# 15P1D_EDA.net
KiCad netlist of a schematic drawn in EasyEDA Pro
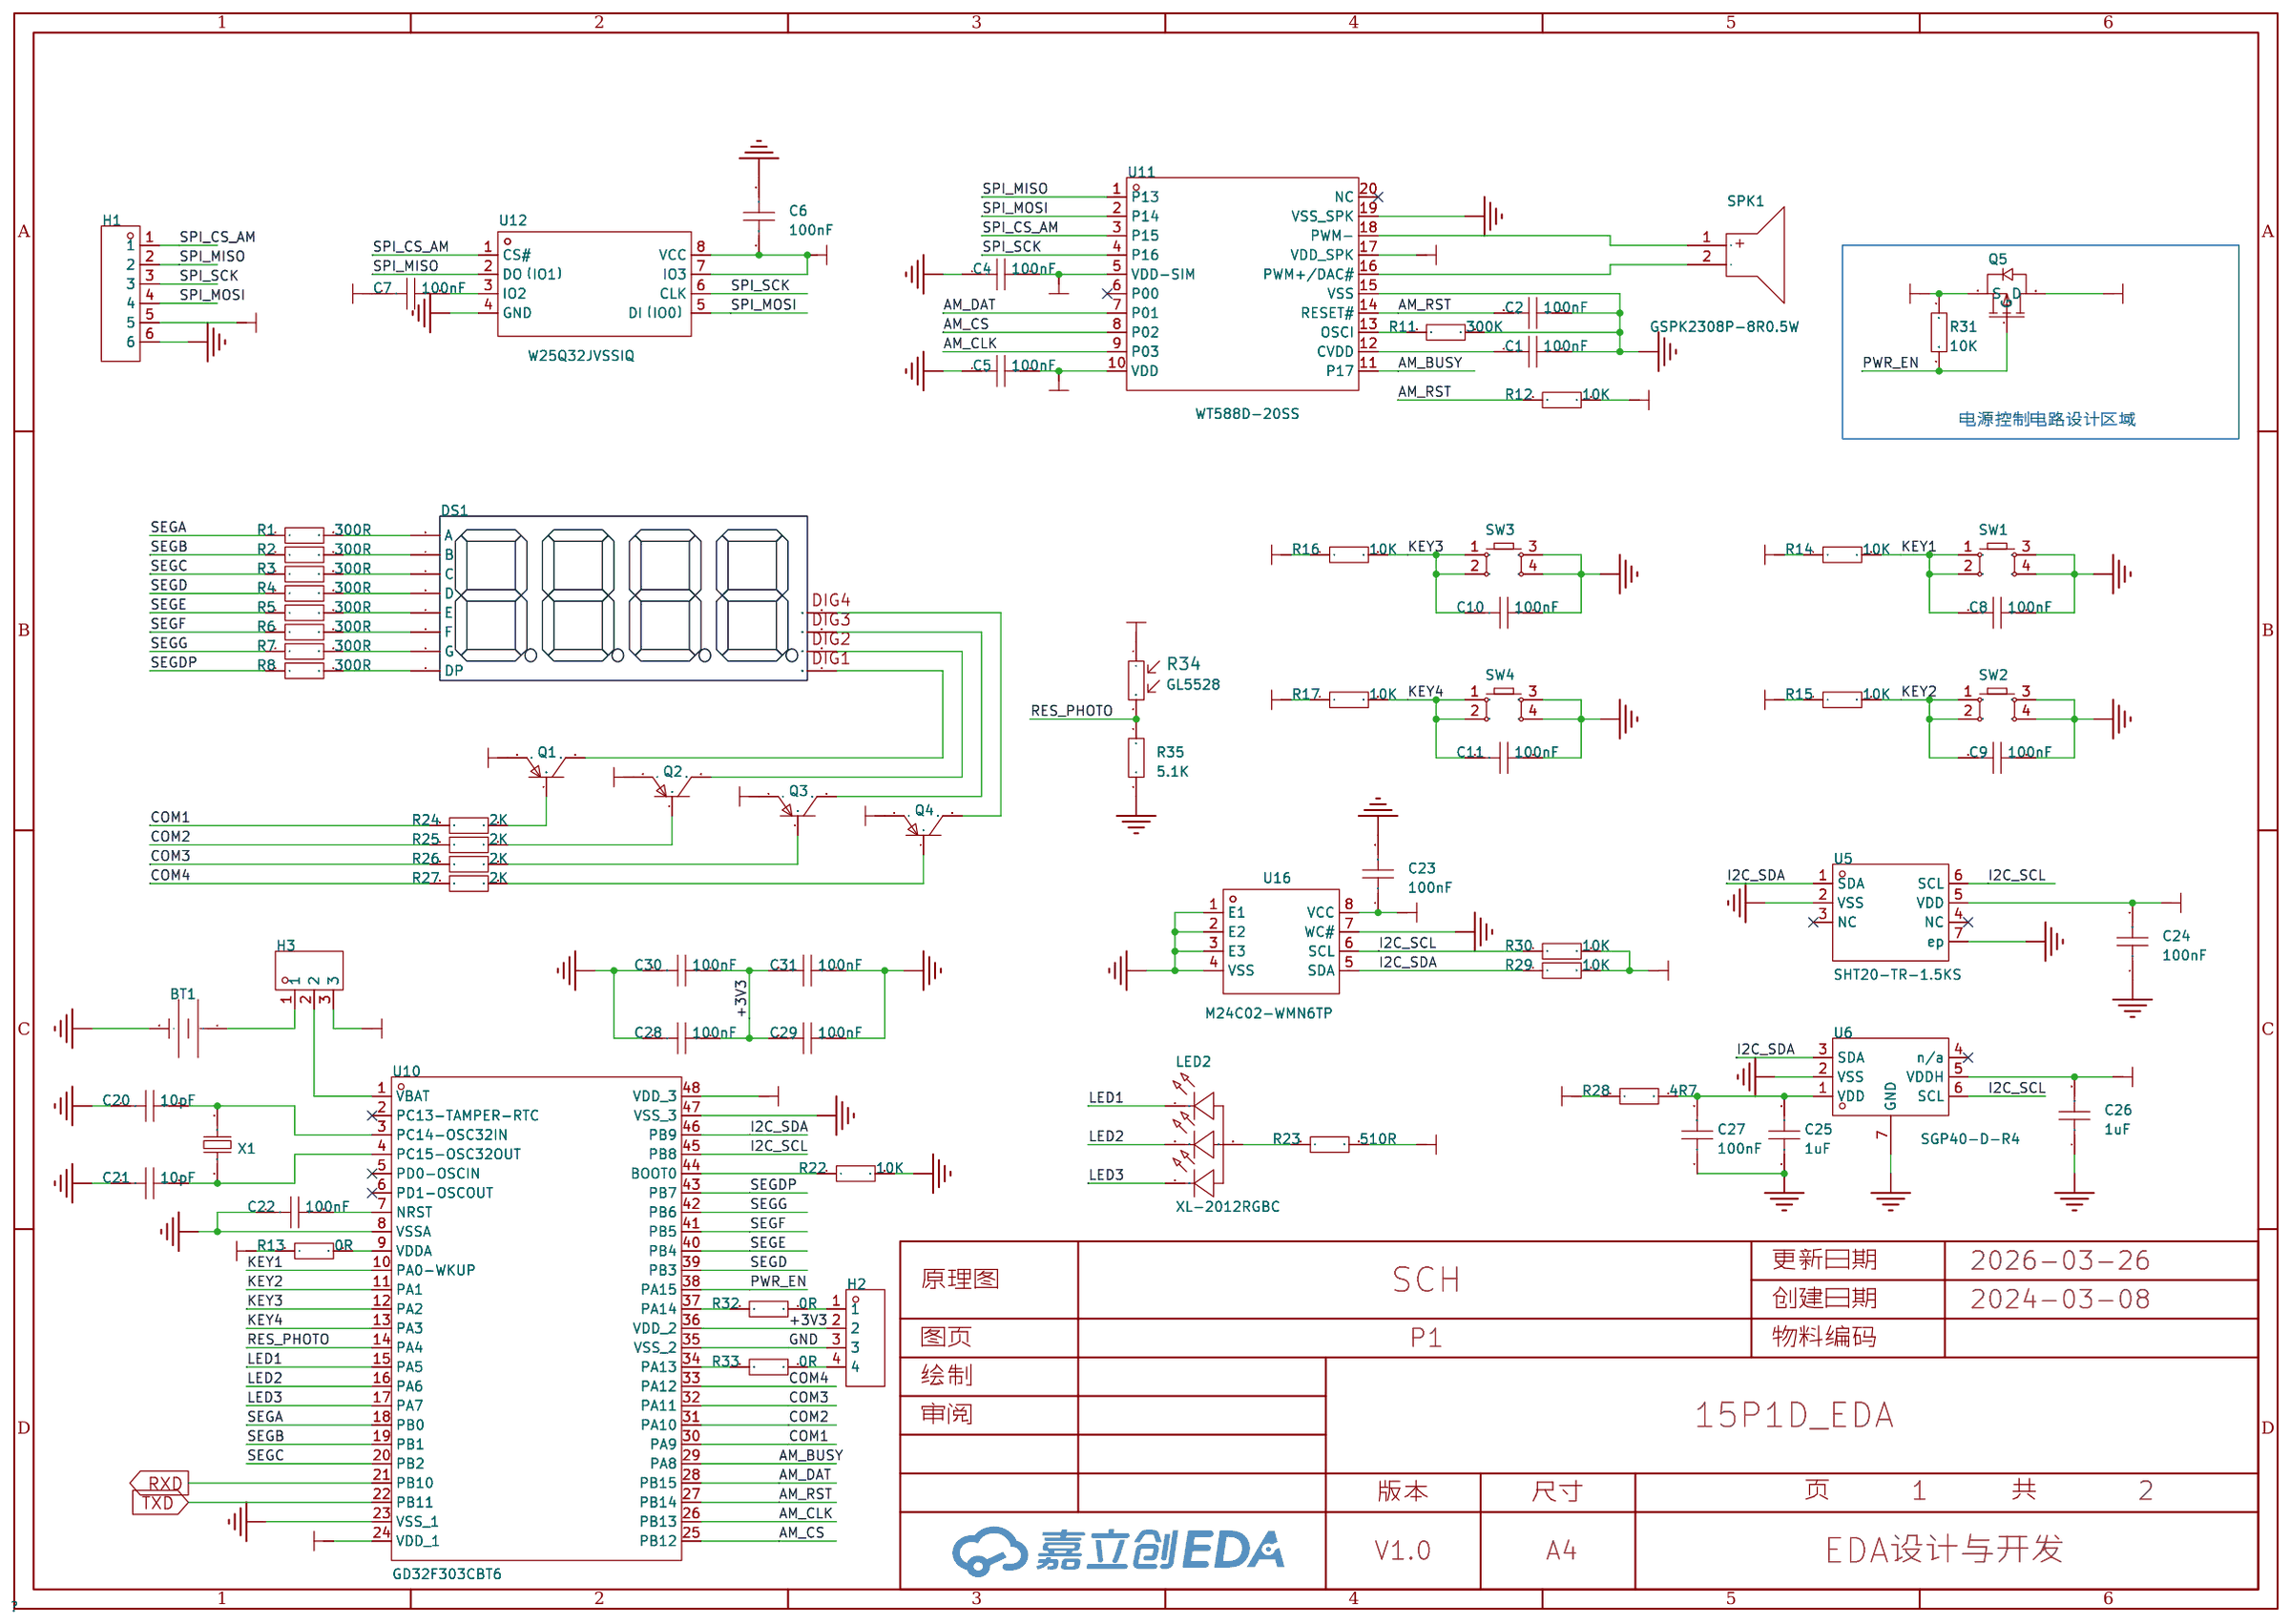
[diagram p0: P1]
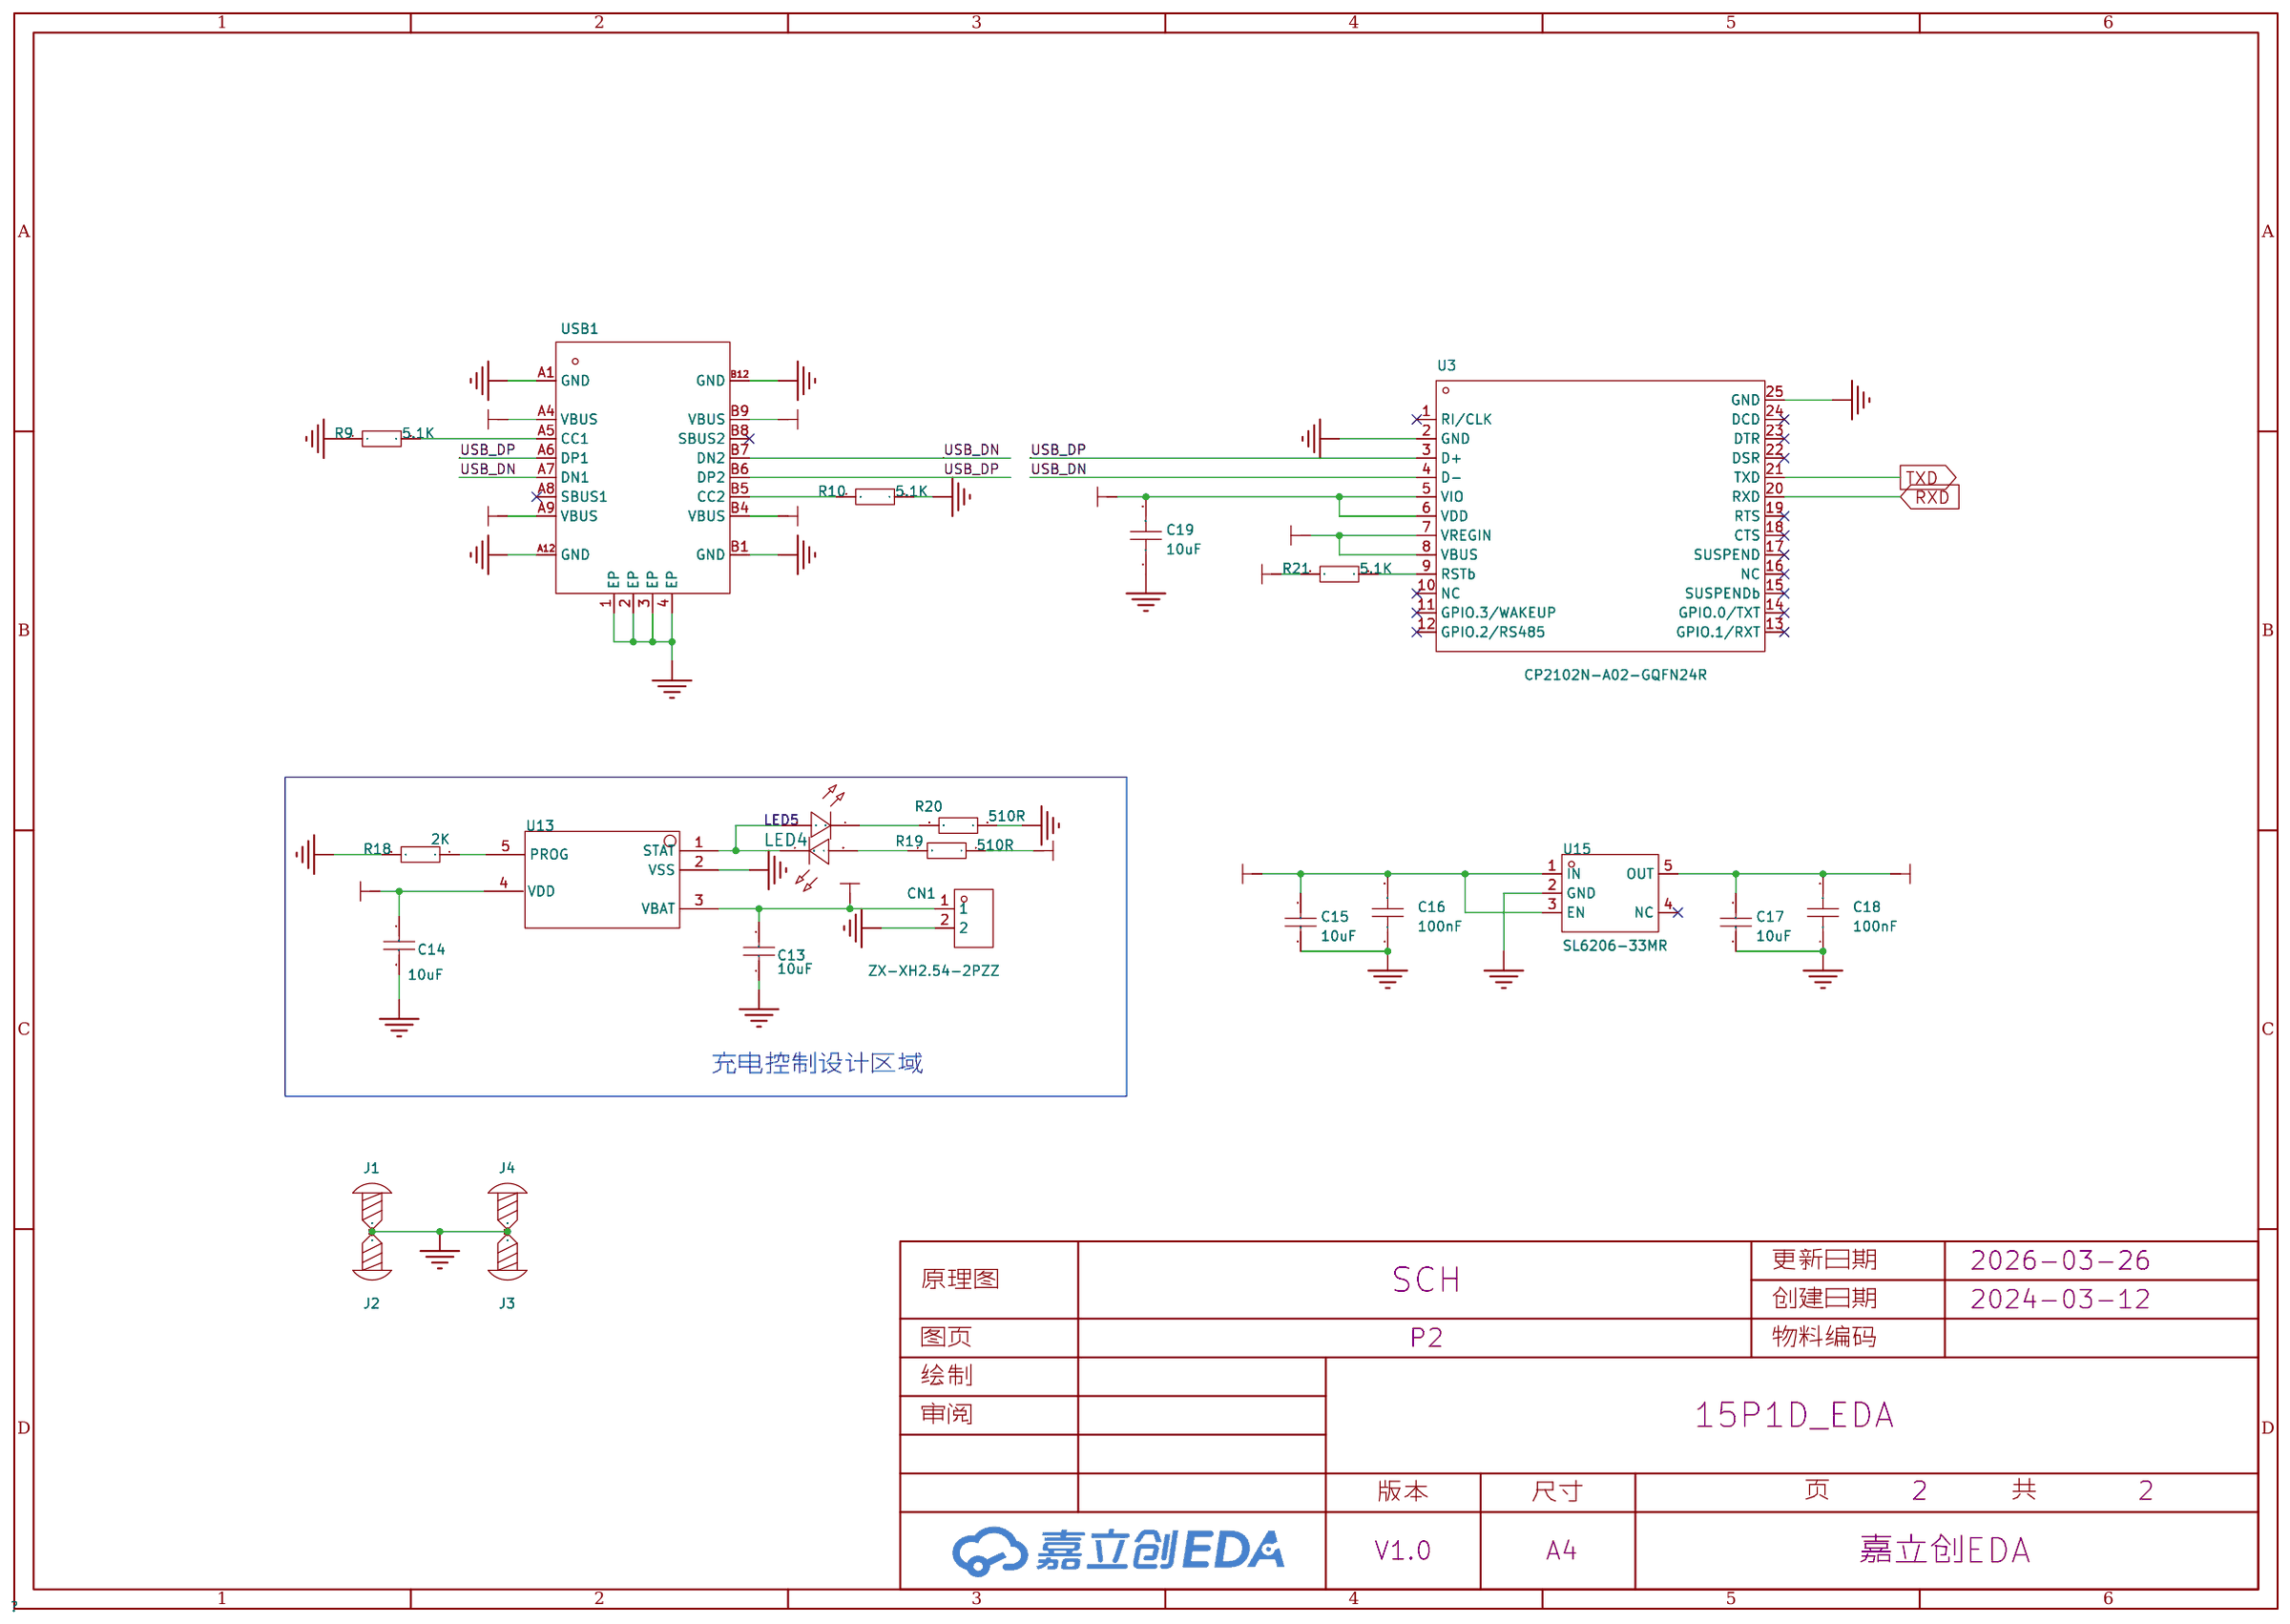
[diagram p1: P2]

(export (version "E")
  (design (tool "Eeschema 10.0.6"))
  (components
    (comp (ref "BT1")
      (value "BS-12-B3AA003")
      (footprint "easyedapro:BAT-SMD_BS-12-B3AA011")
      (description "连接器类型:电池底座;适用电池规格:CR1220;工作温度范围:-25°C~+85°C;")
      (fields (field (name "Manufacturer") "MYOUNG(美阳)"))
      (libsource (lib "easyedapro") (part "BS-12-B3AA003"))
    )
    (comp (ref "C1")
      (value "100nF")
      (footprint "easyedapro:C0805")
      (libsource (lib "easyedapro") (part "CapAcitance"))
    )
    (comp (ref "C2")
      (value "100nF")
      (footprint "easyedapro:C0805")
      (libsource (lib "easyedapro") (part "CapAcitance"))
    )
    (comp (ref "C4")
      (value "100nF")
      (footprint "easyedapro:C0805")
      (libsource (lib "easyedapro") (part "CapAcitance"))
    )
    (comp (ref "C5")
      (value "100nF")
      (footprint "easyedapro:C0805")
      (libsource (lib "easyedapro") (part "CapAcitance"))
    )
    (comp (ref "C6")
      (value "100nF")
      (footprint "easyedapro:C0805")
      (libsource (lib "easyedapro") (part "CapAcitance"))
    )
    (comp (ref "C7")
      (value "100nF")
      (footprint "easyedapro:C0805")
      (libsource (lib "easyedapro") (part "CapAcitance"))
    )
    (comp (ref "C8")
      (value "100nF")
      (footprint "easyedapro:C0805")
      (libsource (lib "easyedapro") (part "CapAcitance"))
    )
    (comp (ref "C9")
      (value "100nF")
      (footprint "easyedapro:C0805")
      (libsource (lib "easyedapro") (part "CapAcitance"))
    )
    (comp (ref "C10")
      (value "100nF")
      (footprint "easyedapro:C0805")
      (libsource (lib "easyedapro") (part "CapAcitance"))
    )
    (comp (ref "C11")
      (value "100nF")
      (footprint "easyedapro:C0805")
      (libsource (lib "easyedapro") (part "CapAcitance"))
    )
    (comp (ref "C20")
      (value "10pF")
      (footprint "easyedapro:C0805")
      (libsource (lib "easyedapro") (part "CapAcitance"))
    )
    (comp (ref "C21")
      (value "10pF")
      (footprint "easyedapro:C0805")
      (libsource (lib "easyedapro") (part "CapAcitance"))
    )
    (comp (ref "C22")
      (value "100nF")
      (footprint "easyedapro:C0805")
      (libsource (lib "easyedapro") (part "CapAcitance"))
    )
    (comp (ref "C23")
      (value "100nF")
      (footprint "easyedapro:C0805")
      (libsource (lib "easyedapro") (part "CapAcitance"))
    )
    (comp (ref "C24")
      (value "100nF")
      (footprint "easyedapro:C0805")
      (libsource (lib "easyedapro") (part "CapAcitance"))
    )
    (comp (ref "C25")
      (value "1uF")
      (footprint "easyedapro:C0805")
      (libsource (lib "easyedapro") (part "CapAcitance"))
    )
    (comp (ref "C26")
      (value "1uF")
      (footprint "easyedapro:C0805")
      (libsource (lib "easyedapro") (part "CapAcitance"))
    )
    (comp (ref "C27")
      (value "100nF")
      (footprint "easyedapro:C0805")
      (libsource (lib "easyedapro") (part "CapAcitance"))
    )
    (comp (ref "C28")
      (value "100nF")
      (footprint "easyedapro:C0805")
      (libsource (lib "easyedapro") (part "CapAcitance"))
    )
    (comp (ref "C29")
      (value "100nF")
      (footprint "easyedapro:C0805")
      (libsource (lib "easyedapro") (part "CapAcitance"))
    )
    (comp (ref "C30")
      (value "100nF")
      (footprint "easyedapro:C0805")
      (libsource (lib "easyedapro") (part "CapAcitance"))
    )
    (comp (ref "C31")
      (value "100nF")
      (footprint "easyedapro:C0805")
      (libsource (lib "easyedapro") (part "CapAcitance"))
    )
    (comp (ref "DS1")
      (value "~")
      (footprint "easyedapro:LED-SEG-TH_FJ5461AH")
      (libsource (lib "easyedapro") (part "LED_SEG_TH_0.56x4"))
    )
    (comp (ref "H1")
      (value "~")
      (footprint "easyedapro:HDR-TH_6P-P2.54-V-F")
      (libsource (lib "easyedapro") (part "Header-Female-2.54_1x6"))
    )
    (comp (ref "H2")
      (value "~")
      (footprint "easyedapro:HDR-TH_4P-P2.54-V-F")
      (libsource (lib "easyedapro") (part "2.54-1*4P母"))
    )
    (comp (ref "H3")
      (value "Jumper3")
      (footprint "easyedapro:HDR-TH_3P-P2.54-V-M-A")
      (libsource (lib "easyedapro") (part "JUMPER3"))
    )
    (comp (ref "LED2")
      (value "XL-2012RGBC")
      (footprint "easyedapro:LED-SMD_4P-L2.0-W1.3-BR")
      (fields (field (name "Manufacturer") "XINGLIGHT(成兴光)"))
      (libsource (lib "easyedapro") (part "XL-2012RGBC"))
    )
    (comp (ref "Q1")
      (value "~")
      (footprint "easyedapro:S8550P_SOT")
      (libsource (lib "easyedapro") (part "PNP"))
    )
    (comp (ref "Q2")
      (value "~")
      (footprint "easyedapro:S8550P_SOT")
      (libsource (lib "easyedapro") (part "PNP"))
    )
    (comp (ref "Q3")
      (value "~")
      (footprint "easyedapro:S8550P_SOT")
      (libsource (lib "easyedapro") (part "PNP"))
    )
    (comp (ref "Q4")
      (value "~")
      (footprint "easyedapro:S8550P_SOT")
      (libsource (lib "easyedapro") (part "PNP"))
    )
    (comp (ref "Q5")
      (value "~")
      (footprint "easyedapro:AO3401A_SOT-23-3")
      (libsource (lib "easyedapro") (part "P_MOS"))
    )
    (comp (ref "R1") (value "300R") (footprint "easyedapro:R0805") (libsource (lib "easyedapro") (part "电阻")))
    (comp (ref "R2") (value "300R") (footprint "easyedapro:R0805") (libsource (lib "easyedapro") (part "电阻")))
    (comp (ref "R3") (value "300R") (footprint "easyedapro:R0805") (libsource (lib "easyedapro") (part "电阻")))
    (comp (ref "R4") (value "300R") (footprint "easyedapro:R0805") (libsource (lib "easyedapro") (part "电阻")))
    (comp (ref "R5") (value "300R") (footprint "easyedapro:R0805") (libsource (lib "easyedapro") (part "电阻")))
    (comp (ref "R6") (value "300R") (footprint "easyedapro:R0805") (libsource (lib "easyedapro") (part "电阻")))
    (comp (ref "R7") (value "300R") (footprint "easyedapro:R0805") (libsource (lib "easyedapro") (part "电阻")))
    (comp (ref "R8") (value "300R") (footprint "easyedapro:R0805") (libsource (lib "easyedapro") (part "电阻")))
    (comp (ref "R11")
      (value "300K")
      (footprint "easyedapro:R0805")
      (libsource (lib "easyedapro") (part "电阻"))
    )
    (comp (ref "R12") (value "10K") (footprint "easyedapro:R0805") (libsource (lib "easyedapro") (part "电阻")))
    (comp (ref "R13") (value "0R") (footprint "easyedapro:R0805") (libsource (lib "easyedapro") (part "电阻")))
    (comp (ref "R14") (value "10K") (footprint "easyedapro:R0805") (libsource (lib "easyedapro") (part "电阻")))
    (comp (ref "R15") (value "10K") (footprint "easyedapro:R0805") (libsource (lib "easyedapro") (part "电阻")))
    (comp (ref "R16") (value "10K") (footprint "easyedapro:R0805") (libsource (lib "easyedapro") (part "电阻")))
    (comp (ref "R17") (value "10K") (footprint "easyedapro:R0805") (libsource (lib "easyedapro") (part "电阻")))
    (comp (ref "R22") (value "10K") (footprint "easyedapro:R0805") (libsource (lib "easyedapro") (part "电阻")))
    (comp (ref "R23")
      (value "510R")
      (footprint "easyedapro:R0805")
      (libsource (lib "easyedapro") (part "电阻"))
    )
    (comp (ref "R24") (value "2K") (footprint "easyedapro:R0805") (libsource (lib "easyedapro") (part "电阻")))
    (comp (ref "R25") (value "2K") (footprint "easyedapro:R0805") (libsource (lib "easyedapro") (part "电阻")))
    (comp (ref "R26") (value "2K") (footprint "easyedapro:R0805") (libsource (lib "easyedapro") (part "电阻")))
    (comp (ref "R27") (value "2K") (footprint "easyedapro:R0805") (libsource (lib "easyedapro") (part "电阻")))
    (comp (ref "R28") (value "4R7") (footprint "easyedapro:R0805") (libsource (lib "easyedapro") (part "电阻")))
    (comp (ref "R29") (value "10K") (footprint "easyedapro:R0805") (libsource (lib "easyedapro") (part "电阻")))
    (comp (ref "R30") (value "10K") (footprint "easyedapro:R0805") (libsource (lib "easyedapro") (part "电阻")))
    (comp (ref "R31") (value "10K") (footprint "easyedapro:R0805") (libsource (lib "easyedapro") (part "电阻")))
    (comp (ref "R32") (value "0R") (footprint "easyedapro:R0805") (libsource (lib "easyedapro") (part "电阻")))
    (comp (ref "R33") (value "0R") (footprint "easyedapro:R0805") (libsource (lib "easyedapro") (part "电阻")))
    (comp (ref "R34")
      (value "GL5528")
      (footprint "easyedapro:RES-TH_L5.1-W4.3-P3.40-D0.5")
      (description "暗电阻:1MΩ;亮电阻 @ 10Lux:8kΩ~20kΩ;光谱峰值(波长):540nm;")
      (fields (field (name "Manufacturer") "森霸"))
      (libsource (lib "easyedapro") (part "GL5528"))
    )
    (comp (ref "R35")
      (value "5.1K")
      (footprint "easyedapro:R0805")
      (libsource (lib "easyedapro") (part "电阻"))
    )
    (comp (ref "SPK1")
      (value "GSPK2308P-8R0.5W")
      (footprint "easyedapro:SPK-TH_BD23.0-P10.00-D0.8-L-RD")
      (fields (field (name "Manufacturer") "INGHAi(赢海)"))
      (libsource (lib "easyedapro") (part "GSPK2308P-8R0.5W"))
    )
    (comp (ref "SW1")
      (value "~")
      (footprint "easyedapro:Key_SMD_12x12x7.3")
      (libsource (lib "easyedapro") (part "轻触按键"))
    )
    (comp (ref "SW2")
      (value "~")
      (footprint "easyedapro:Key_SMD_12x12x7.3")
      (libsource (lib "easyedapro") (part "轻触按键"))
    )
    (comp (ref "SW3")
      (value "~")
      (footprint "easyedapro:Key_SMD_12x12x7.3")
      (libsource (lib "easyedapro") (part "轻触按键"))
    )
    (comp (ref "SW4")
      (value "~")
      (footprint "easyedapro:Key_SMD_12x12x7.3")
      (libsource (lib "easyedapro") (part "轻触按键"))
    )
    (comp (ref "U5")
      (value "SHT20-TR-1.5KS")
      (footprint "easyedapro:DFN-6_L3.0-W3.0-P0.95-TR-EP")
      (description "接口类型:I2C;")
      (fields (field (name "Manufacturer") "Sensirion(瑞士盛思锐)"))
      (libsource (lib "easyedapro") (part "SHT20"))
    )
    (comp (ref "U6")
      (value "SGP40-D-R4")
      (footprint "easyedapro:DFN-6_L2.4-W2.4-P0.80-TL-EP")
      (description "气体类型:空气质量;精度:-;")
      (fields (field (name "Manufacturer") "Sensirion(瑞士盛思锐)"))
      (libsource (lib "easyedapro") (part "SGP40-D-R4"))
    )
    (comp (ref "U10")
      (value "GD32F303CBT6")
      (footprint "easyedapro:LQFP-48_L7.0-W7.0-P0.50-LS9.0-BL")
      (description "CPU内核:CM4;程序存储容量:128KB;RAM总容量:32KB;GPIO端口数量:37;工作电压范围:-;CPU最大主频:120MHz;程序存储器类型:FLASH;")
      (fields (field (name "Manufacturer") "GigaDevice(兆易创新)"))
      (libsource (lib "easyedapro") (part "GD32F303CBT6"))
    )
    (comp (ref "U11")
      (value "WT588D-20SS")
      (footprint "easyedapro:SSOP-20_L7.2-W5.3-P0.65-LS7.8-BL")
      (description "高品质语音芯片")
      (fields (field (name "Manufacturer") "WT(唯创知音)"))
      (libsource (lib "easyedapro") (part "WT588D"))
    )
    (comp (ref "U12")
      (value "W25Q32JVSSIQ")
      (footprint "easyedapro:SOIC-8_L5.3-W5.3-P1.27-LS8.0-BL")
      (description "接口类型:SPI;存储容量:32Mbit;")
      (fields (field (name "Manufacturer") "WINBOND(华邦)"))
      (libsource (lib "easyedapro") (part "W25Q32JVSSIQ"))
    )
    (comp (ref "U16")
      (value "M24C02-WMN6TP")
      (footprint "easyedapro:SOIC-8_L4.9-W3.9-P1.27-LS6.0-BL")
      (description "接口类型:I2C;存储容量:2Kbit;")
      (fields (field (name "Manufacturer") "ST(意法半导体)"))
      (libsource (lib "easyedapro") (part "M24C02-WMN6TP"))
    )
    (comp (ref "X1")
      (value "32.768kHz")
      (footprint "easyedapro:FC-135R_L3.2-W1.5")
      (description "晶振类型:贴片晶振;频率:32.768kHz;常温频差:±20ppm;外接负载电容:12.5pF;")
      (fields (field (name "Manufacturer Part") "Q13FC13500004") (field (name "Manufacturer") "EPSON(爱普生)"))
      (libsource (lib "easyedapro") (part "Q13FC1350000400"))
    )
    (comp (ref "C13")
      (value "10uF")
      (footprint "easyedapro:C1206")
      (description "容值:10uF;精度:±10%;额定电压:50V;材质(温度系数):X5R;")
      (fields
        (field (name "Manufacturer Part") "CL31A106KBHNNNE")
        (field (name "Manufacturer") "SAMSUNG(三星)")
      )
      (libsource (lib "easyedapro") (part "CL31A106KBHNNNE"))
    )
    (comp (ref "C14")
      (value "10uF")
      (footprint "easyedapro:C1206")
      (description "容值:10uF;精度:±10%;额定电压:50V;材质(温度系数):X5R;")
      (fields
        (field (name "Manufacturer Part") "CL31A106KBHNNNE")
        (field (name "Manufacturer") "SAMSUNG(三星)")
      )
      (libsource (lib "easyedapro") (part "CL31A106KBHNNNE"))
    )
    (comp (ref "C15")
      (value "10uF")
      (footprint "easyedapro:C1206")
      (description "容值:10uF;精度:±10%;额定电压:50V;材质(温度系数):X5R;")
      (fields
        (field (name "Manufacturer Part") "CL31A106KBHNNNE")
        (field (name "Manufacturer") "SAMSUNG(三星)")
      )
      (libsource (lib "easyedapro") (part "CL31A106KBHNNNE"))
    )
    (comp (ref "C16")
      (value "100nF")
      (footprint "easyedapro:C0805")
      (libsource (lib "easyedapro") (part "CapAcitance"))
    )
    (comp (ref "C17")
      (value "10uF")
      (footprint "easyedapro:C1206")
      (description "容值:10uF;精度:±10%;额定电压:50V;材质(温度系数):X5R;")
      (fields
        (field (name "Manufacturer Part") "CL31A106KBHNNNE")
        (field (name "Manufacturer") "SAMSUNG(三星)")
      )
      (libsource (lib "easyedapro") (part "CL31A106KBHNNNE"))
    )
    (comp (ref "C18")
      (value "100nF")
      (footprint "easyedapro:C0805")
      (libsource (lib "easyedapro") (part "CapAcitance"))
    )
    (comp (ref "C19")
      (value "10uF")
      (footprint "easyedapro:C0805")
      (libsource (lib "easyedapro") (part "CapAcitance"))
    )
    (comp (ref "CN1")
      (value "ZX-XH2.54-2PZZ")
      (footprint "easyedapro:CONN-TH_2P-P2.50_HX25003-2A")
      (fields (field (name "Manufacturer") "Megastar(兆星)"))
      (libsource (lib "easyedapro") (part "ZX-XH2.54-2PZZ"))
    )
    (comp (ref "J1") (value "~") (footprint "easyedapro:M2螺丝") (libsource (lib "easyedapro") (part "螺丝孔")))
    (comp (ref "J2") (value "~") (footprint "easyedapro:M2螺丝") (libsource (lib "easyedapro") (part "螺丝孔")))
    (comp (ref "J3") (value "~") (footprint "easyedapro:M2螺丝") (libsource (lib "easyedapro") (part "螺丝孔")))
    (comp (ref "J4") (value "~") (footprint "easyedapro:M2螺丝") (libsource (lib "easyedapro") (part "螺丝孔")))
    (comp (ref "LED4")
      (value "~")
      (footprint "easyedapro:LED_0805")
      (libsource (lib "easyedapro") (part "LED_R"))
    )
    (comp (ref "LED5")
      (value "~")
      (footprint "easyedapro:LED_0805")
      (libsource (lib "easyedapro") (part "LED_G"))
    )
    (comp (ref "R9") (value "5.1K") (footprint "easyedapro:R0805") (libsource (lib "easyedapro") (part "电阻")))
    (comp (ref "R10")
      (value "5.1K")
      (footprint "easyedapro:R0805")
      (libsource (lib "easyedapro") (part "电阻"))
    )
    (comp (ref "R18") (value "2K") (footprint "easyedapro:R0805") (libsource (lib "easyedapro") (part "电阻")))
    (comp (ref "R19")
      (value "510R")
      (footprint "easyedapro:R0805")
      (libsource (lib "easyedapro") (part "电阻"))
    )
    (comp (ref "R20")
      (value "510R")
      (footprint "easyedapro:R0805")
      (libsource (lib "easyedapro") (part "电阻"))
    )
    (comp (ref "R21")
      (value "5.1K")
      (footprint "easyedapro:R0805")
      (libsource (lib "easyedapro") (part "电阻"))
    )
    (comp (ref "U3")
      (value "CP2102N-A02-GQFN24R")
      (footprint "easyedapro:QFN-24_L4.0-W4.0-P0.50-TL-EP2.6")
      (description "应用功能:USB转UART;接口协议:UART;")
      (fields (field (name "Manufacturer") "SKYWORKS/SILICON LABS(芯科)"))
      (libsource (lib "easyedapro") (part "CP2102N-A02-GQFN24R"))
    )
    (comp (ref "U13") (value "~") (libsource (lib "easyedapro") (part "BCON")))
    (comp (ref "U15")
      (value "SL6206-33MR")
      (footprint "easyedapro:SOT-23-5_L2.9-W1.6-P0.95-LS2.8-BL")
      (description "输出类型:-;")
      (fields (field (name "Manufacturer") "Slkor(萨科微)"))
      (libsource (lib "easyedapro") (part "SL6206-33MR"))
    )
    (comp (ref "USB1")
      (value "~")
      (footprint "easyedapro:USB_TYPE-C-16P")
      (libsource (lib "easyedapro") (part "USB_TYPE-C-16P"))
    )
  )
  (nets
    (net (code "1") (name "+3V3") (class "Default")
      (node (ref "C17") (pin "2") (pinfunction "2_2") (pintype "input"))
      (node (ref "C18") (pin "2") (pinfunction "2_2") (pintype "input"))
      (node (ref "C19") (pin "2") (pinfunction "2_2") (pintype "input"))
      (node (ref "C23") (pin "1") (pinfunction "1_1") (pintype "input"))
      (node (ref "C28") (pin "1") (pinfunction "1_1") (pintype "input"))
      (node (ref "C29") (pin "2") (pinfunction "2_2") (pintype "input"))
      (node (ref "C30") (pin "1") (pinfunction "1_1") (pintype "input"))
      (node (ref "C31") (pin "2") (pinfunction "2_2") (pintype "input"))
      (node (ref "C4") (pin "2") (pinfunction "2_2") (pintype "input"))
      (node (ref "C5") (pin "2") (pinfunction "2_2") (pintype "input"))
      (node (ref "C6") (pin "2") (pinfunction "2_2") (pintype "input"))
      (node (ref "C7") (pin "1") (pinfunction "1_1") (pintype "input"))
      (node (ref "H1") (pin "5") (pinfunction "5_5") (pintype "unspecified"))
      (node (ref "H2") (pin "2") (pinfunction "2_2") (pintype "unspecified"))
      (node (ref "H3") (pin "3") (pinfunction "3_3") (pintype "input"))
      (node (ref "Q1") (pin "2") (pinfunction "E_2") (pintype "input"))
      (node (ref "Q2") (pin "2") (pinfunction "E_2") (pintype "input"))
      (node (ref "Q3") (pin "2") (pinfunction "E_2") (pintype "input"))
      (node (ref "Q4") (pin "2") (pinfunction "E_2") (pintype "input"))
      (node (ref "Q5") (pin "2") (pinfunction "S_2") (pintype "input"))
      (node (ref "R12") (pin "2") (pinfunction "2_2") (pintype "input"))
      (node (ref "R13") (pin "1") (pinfunction "1_1") (pintype "input"))
      (node (ref "R14") (pin "1") (pinfunction "1_1") (pintype "input"))
      (node (ref "R15") (pin "1") (pinfunction "1_1") (pintype "input"))
      (node (ref "R16") (pin "1") (pinfunction "1_1") (pintype "input"))
      (node (ref "R17") (pin "1") (pinfunction "1_1") (pintype "input"))
      (node (ref "R21") (pin "2") (pinfunction "2_2") (pintype "input"))
      (node (ref "R23") (pin "2") (pinfunction "2_2") (pintype "input"))
      (node (ref "R29") (pin "2") (pinfunction "2_2") (pintype "input"))
      (node (ref "R30") (pin "2") (pinfunction "2_2") (pintype "input"))
      (node (ref "R31") (pin "1") (pinfunction "1_1") (pintype "input"))
      (node (ref "R34") (pin "1") (pinfunction "1_1") (pintype "input"))
      (node (ref "U10") (pin "24") (pinfunction "VDD_1_24") (pintype "unspecified"))
      (node (ref "U10") (pin "36") (pinfunction "VDD_2_36") (pintype "unspecified"))
      (node (ref "U10") (pin "48") (pinfunction "VDD_3_48") (pintype "unspecified"))
      (node (ref "U11") (pin "10") (pinfunction "VDD_10") (pintype "input"))
      (node (ref "U11") (pin "17") (pinfunction "VDD_SPK_17") (pintype "input"))
      (node (ref "U11") (pin "5") (pinfunction "VDD-SIM_5") (pintype "input"))
      (node (ref "U12") (pin "7") (pinfunction "IO3_7") (pintype "unspecified"))
      (node (ref "U12") (pin "8") (pinfunction "VCC_8") (pintype "unspecified"))
      (node (ref "U15") (pin "5") (pinfunction "OUT_5") (pintype "unspecified"))
      (node (ref "U16") (pin "8") (pinfunction "VCC_8") (pintype "unspecified"))
      (node (ref "U3") (pin "5") (pinfunction "VIO_5") (pintype "unspecified"))
      (node (ref "U3") (pin "6") (pinfunction "VDD_6") (pintype "unspecified"))
    )
    (net (code "2") (name "+VS") (class "Default")
      (node (ref "C24") (pin "2") (pinfunction "2_2") (pintype "input"))
      (node (ref "C26") (pin "2") (pinfunction "2_2") (pintype "input"))
      (node (ref "Q5") (pin "3") (pinfunction "D_3") (pintype "input"))
      (node (ref "R28") (pin "1") (pinfunction "1_1") (pintype "input"))
      (node (ref "U5") (pin "5") (pinfunction "VDD_5") (pintype "unspecified"))
      (node (ref "U6") (pin "5") (pinfunction "VDDH_5") (pintype "unspecified"))
    )
    (net (code "3") (name "AM_BUSY") (class "Default")
      (node (ref "U10") (pin "29") (pinfunction "PA8_29") (pintype "unspecified"))
      (node (ref "U11") (pin "11") (pinfunction "P17_11") (pintype "input"))
    )
    (net (code "4") (name "AM_CLK") (class "Default")
      (node (ref "U10") (pin "26") (pinfunction "PB13_26") (pintype "unspecified"))
      (node (ref "U11") (pin "9") (pinfunction "P03_9") (pintype "input"))
    )
    (net (code "5") (name "AM_CS") (class "Default")
      (node (ref "U10") (pin "25") (pinfunction "PB12_25") (pintype "unspecified"))
      (node (ref "U11") (pin "8") (pinfunction "P02_8") (pintype "input"))
    )
    (net (code "6") (name "AM_DAT") (class "Default")
      (node (ref "U10") (pin "28") (pinfunction "PB15_28") (pintype "unspecified"))
      (node (ref "U11") (pin "7") (pinfunction "P01_7") (pintype "input"))
    )
    (net (code "7") (name "AM_RST") (class "Default")
      (node (ref "C2") (pin "1") (pinfunction "1_1") (pintype "input"))
      (node (ref "R12") (pin "1") (pinfunction "1_1") (pintype "input"))
      (node (ref "U10") (pin "27") (pinfunction "PB14_27") (pintype "unspecified"))
      (node (ref "U11") (pin "14") (pinfunction "RESET#_14") (pintype "input"))
    )
    (net (code "8") (name "COM1") (class "Default")
      (node (ref "R24") (pin "1") (pinfunction "1_1") (pintype "input"))
      (node (ref "U10") (pin "30") (pinfunction "PA9_30") (pintype "unspecified"))
    )
    (net (code "9") (name "COM2") (class "Default")
      (node (ref "R25") (pin "1") (pinfunction "1_1") (pintype "input"))
      (node (ref "U10") (pin "31") (pinfunction "PA10_31") (pintype "unspecified"))
    )
    (net (code "10") (name "COM3") (class "Default")
      (node (ref "R26") (pin "1") (pinfunction "1_1") (pintype "input"))
      (node (ref "U10") (pin "32") (pinfunction "PA11_32") (pintype "unspecified"))
    )
    (net (code "11") (name "COM4") (class "Default")
      (node (ref "R27") (pin "1") (pinfunction "1_1") (pintype "input"))
      (node (ref "U10") (pin "33") (pinfunction "PA12_33") (pintype "unspecified"))
    )
    (net (code "12") (name "GND") (class "Default")
      (node (ref "BT1") (pin "2") (pinfunction "-_2") (pintype "unspecified"))
      (node (ref "C1") (pin "2") (pinfunction "2_2") (pintype "input"))
      (node (ref "C10") (pin "2") (pinfunction "2_2") (pintype "input"))
      (node (ref "C11") (pin "2") (pinfunction "2_2") (pintype "input"))
      (node (ref "C13") (pin "2") (pinfunction "2_2") (pintype "input"))
      (node (ref "C14") (pin "2") (pinfunction "2_2") (pintype "input"))
      (node (ref "C15") (pin "1") (pinfunction "1_1") (pintype "input"))
      (node (ref "C16") (pin "1") (pinfunction "1_1") (pintype "input"))
      (node (ref "C17") (pin "1") (pinfunction "1_1") (pintype "input"))
      (node (ref "C18") (pin "1") (pinfunction "1_1") (pintype "input"))
      (node (ref "C19") (pin "1") (pinfunction "1_1") (pintype "input"))
      (node (ref "C2") (pin "2") (pinfunction "2_2") (pintype "input"))
      (node (ref "C20") (pin "1") (pinfunction "1_1") (pintype "input"))
      (node (ref "C21") (pin "1") (pinfunction "1_1") (pintype "input"))
      (node (ref "C22") (pin "1") (pinfunction "1_1") (pintype "input"))
      (node (ref "C23") (pin "2") (pinfunction "2_2") (pintype "input"))
      (node (ref "C24") (pin "1") (pinfunction "1_1") (pintype "input"))
      (node (ref "C25") (pin "1") (pinfunction "1_1") (pintype "input"))
      (node (ref "C26") (pin "1") (pinfunction "1_1") (pintype "input"))
      (node (ref "C27") (pin "1") (pinfunction "1_1") (pintype "input"))
      (node (ref "C28") (pin "2") (pinfunction "2_2") (pintype "input"))
      (node (ref "C29") (pin "1") (pinfunction "1_1") (pintype "input"))
      (node (ref "C30") (pin "2") (pinfunction "2_2") (pintype "input"))
      (node (ref "C31") (pin "1") (pinfunction "1_1") (pintype "input"))
      (node (ref "C4") (pin "1") (pinfunction "1_1") (pintype "input"))
      (node (ref "C5") (pin "1") (pinfunction "1_1") (pintype "input"))
      (node (ref "C6") (pin "1") (pinfunction "1_1") (pintype "input"))
      (node (ref "C8") (pin "2") (pinfunction "2_2") (pintype "input"))
      (node (ref "C9") (pin "2") (pinfunction "2_2") (pintype "input"))
      (node (ref "CN1") (pin "2") (pinfunction "2_2") (pintype "unspecified"))
      (node (ref "H1") (pin "6") (pinfunction "6_6") (pintype "unspecified"))
      (node (ref "H2") (pin "3") (pinfunction "3_3") (pintype "unspecified"))
      (node (ref "J1") (pin "1") (pinfunction "1_1") (pintype "input"))
      (node (ref "J2") (pin "1") (pinfunction "1_1") (pintype "input"))
      (node (ref "J3") (pin "1") (pinfunction "1_1") (pintype "input"))
      (node (ref "J4") (pin "1") (pinfunction "1_1") (pintype "input"))
      (node (ref "R10") (pin "1") (pinfunction "1_1") (pintype "input"))
      (node (ref "R11") (pin "2") (pinfunction "2_2") (pintype "input"))
      (node (ref "R18") (pin "2") (pinfunction "2_2") (pintype "input"))
      (node (ref "R20") (pin "1") (pinfunction "1_1") (pintype "input"))
      (node (ref "R22") (pin "2") (pinfunction "2_2") (pintype "input"))
      (node (ref "R35") (pin "2") (pinfunction "2_2") (pintype "input"))
      (node (ref "R9") (pin "1") (pinfunction "1_1") (pintype "input"))
      (node (ref "SW1") (pin "3") (pinfunction "3_3") (pintype "input"))
      (node (ref "SW1") (pin "4") (pinfunction "4_4") (pintype "input"))
      (node (ref "SW2") (pin "3") (pinfunction "3_3") (pintype "input"))
      (node (ref "SW2") (pin "4") (pinfunction "4_4") (pintype "input"))
      (node (ref "SW3") (pin "3") (pinfunction "3_3") (pintype "input"))
      (node (ref "SW3") (pin "4") (pinfunction "4_4") (pintype "input"))
      (node (ref "SW4") (pin "3") (pinfunction "3_3") (pintype "input"))
      (node (ref "SW4") (pin "4") (pinfunction "4_4") (pintype "input"))
      (node (ref "U10") (pin "23") (pinfunction "VSS_1_23") (pintype "unspecified"))
      (node (ref "U10") (pin "35") (pinfunction "VSS_2_35") (pintype "unspecified"))
      (node (ref "U10") (pin "47") (pinfunction "VSS_3_47") (pintype "unspecified"))
      (node (ref "U10") (pin "8") (pinfunction "VSSA_8") (pintype "unspecified"))
      (node (ref "U11") (pin "15") (pinfunction "VSS_15") (pintype "input"))
      (node (ref "U11") (pin "19") (pinfunction "VSS_SPK_19") (pintype "input"))
      (node (ref "U12") (pin "4") (pinfunction "GND_4") (pintype "unspecified"))
      (node (ref "U13") (pin "2") (pinfunction "VSS_2") (pintype "input"))
      (node (ref "U15") (pin "2") (pinfunction "GND_2") (pintype "unspecified"))
      (node (ref "U16") (pin "1") (pinfunction "E1_1") (pintype "unspecified"))
      (node (ref "U16") (pin "2") (pinfunction "E2_2") (pintype "unspecified"))
      (node (ref "U16") (pin "3") (pinfunction "E3_3") (pintype "unspecified"))
      (node (ref "U16") (pin "4") (pinfunction "VSS_4") (pintype "unspecified"))
      (node (ref "U16") (pin "7") (pinfunction "WC#_7") (pintype "unspecified"))
      (node (ref "U3") (pin "2") (pinfunction "GND_2") (pintype "unspecified"))
      (node (ref "U3") (pin "25") (pinfunction "GND_25") (pintype "unspecified"))
      (node (ref "U5") (pin "2") (pinfunction "VSS_2") (pintype "unspecified"))
      (node (ref "U5") (pin "7") (pinfunction "ep_7") (pintype "unspecified"))
      (node (ref "U6") (pin "2") (pinfunction "VSS_2") (pintype "unspecified"))
      (node (ref "U6") (pin "7") (pinfunction "GND_7") (pintype "unspecified"))
      (node (ref "USB1") (pin "1") (pinfunction "EP_1") (pintype "input"))
      (node (ref "USB1") (pin "2") (pinfunction "EP_2") (pintype "input"))
      (node (ref "USB1") (pin "3") (pinfunction "EP_3") (pintype "input"))
      (node (ref "USB1") (pin "4") (pinfunction "EP_4") (pintype "input"))
      (node (ref "USB1") (pin "A1") (pinfunction "GND_A1") (pintype "input"))
      (node (ref "USB1") (pin "A12") (pinfunction "GND_A12") (pintype "input"))
      (node (ref "USB1") (pin "B1") (pinfunction "GND_B1") (pintype "input"))
      (node (ref "USB1") (pin "B12") (pinfunction "GND_B12") (pintype "input"))
    )
    (net (code "13") (name "I2C_SCL") (class "Default")
      (node (ref "R30") (pin "1") (pinfunction "1_1") (pintype "input"))
      (node (ref "U10") (pin "45") (pinfunction "PB8_45") (pintype "unspecified"))
      (node (ref "U16") (pin "6") (pinfunction "SCL_6") (pintype "unspecified"))
      (node (ref "U5") (pin "6") (pinfunction "SCL_6") (pintype "unspecified"))
      (node (ref "U6") (pin "6") (pinfunction "SCL_6") (pintype "unspecified"))
    )
    (net (code "14") (name "I2C_SDA") (class "Default")
      (node (ref "R29") (pin "1") (pinfunction "1_1") (pintype "input"))
      (node (ref "U10") (pin "46") (pinfunction "PB9_46") (pintype "unspecified"))
      (node (ref "U16") (pin "5") (pinfunction "SDA_5") (pintype "unspecified"))
      (node (ref "U5") (pin "1") (pinfunction "SDA_1") (pintype "unspecified"))
      (node (ref "U6") (pin "3") (pinfunction "SDA_3") (pintype "unspecified"))
    )
    (net (code "15") (name "KEY1") (class "Default")
      (node (ref "C8") (pin "1") (pinfunction "1_1") (pintype "input"))
      (node (ref "R14") (pin "2") (pinfunction "2_2") (pintype "input"))
      (node (ref "SW1") (pin "1") (pinfunction "1_1") (pintype "input"))
      (node (ref "SW1") (pin "2") (pinfunction "2_2") (pintype "input"))
      (node (ref "U10") (pin "10") (pinfunction "PA0-WKUP_10") (pintype "unspecified"))
    )
    (net (code "16") (name "KEY2") (class "Default")
      (node (ref "C9") (pin "1") (pinfunction "1_1") (pintype "input"))
      (node (ref "R15") (pin "2") (pinfunction "2_2") (pintype "input"))
      (node (ref "SW2") (pin "1") (pinfunction "1_1") (pintype "input"))
      (node (ref "SW2") (pin "2") (pinfunction "2_2") (pintype "input"))
      (node (ref "U10") (pin "11") (pinfunction "PA1_11") (pintype "unspecified"))
    )
    (net (code "17") (name "KEY3") (class "Default")
      (node (ref "C10") (pin "1") (pinfunction "1_1") (pintype "input"))
      (node (ref "R16") (pin "2") (pinfunction "2_2") (pintype "input"))
      (node (ref "SW3") (pin "1") (pinfunction "1_1") (pintype "input"))
      (node (ref "SW3") (pin "2") (pinfunction "2_2") (pintype "input"))
      (node (ref "U10") (pin "12") (pinfunction "PA2_12") (pintype "unspecified"))
    )
    (net (code "18") (name "KEY4") (class "Default")
      (node (ref "C11") (pin "1") (pinfunction "1_1") (pintype "input"))
      (node (ref "R17") (pin "2") (pinfunction "2_2") (pintype "input"))
      (node (ref "SW4") (pin "1") (pinfunction "1_1") (pintype "input"))
      (node (ref "SW4") (pin "2") (pinfunction "2_2") (pintype "input"))
      (node (ref "U10") (pin "13") (pinfunction "PA3_13") (pintype "unspecified"))
    )
    (net (code "19") (name "LED1") (class "Default")
      (node (ref "LED2") (pin "1") (pinfunction "1_1") (pintype "unspecified"))
      (node (ref "U10") (pin "15") (pinfunction "PA5_15") (pintype "unspecified"))
    )
    (net (code "20") (name "LED2") (class "Default")
      (node (ref "LED2") (pin "2") (pinfunction "2_2") (pintype "unspecified"))
      (node (ref "U10") (pin "16") (pinfunction "PA6_16") (pintype "unspecified"))
    )
    (net (code "21") (name "LED3") (class "Default")
      (node (ref "LED2") (pin "4") (pinfunction "4_4") (pintype "unspecified"))
      (node (ref "U10") (pin "17") (pinfunction "PA7_17") (pintype "unspecified"))
    )
    (net (code "22") (name "Net-(BT1-+)") (class "Default")
      (node (ref "BT1") (pin "1") (pinfunction "+_1") (pintype "unspecified"))
      (node (ref "H3") (pin "1") (pinfunction "1_1") (pintype "input"))
    )
    (net (code "23") (name "Net-(DS1-A)") (class "Default")
      (node (ref "DS1") (pin "11") (pinfunction "A_11") (pintype "input"))
      (node (ref "R1") (pin "2") (pinfunction "2_2") (pintype "input"))
    )
    (net (code "24") (name "Net-(DS1-B)") (class "Default")
      (node (ref "DS1") (pin "7") (pinfunction "B_7") (pintype "input"))
      (node (ref "R2") (pin "2") (pinfunction "2_2") (pintype "input"))
    )
    (net (code "25") (name "Net-(DS1-C)") (class "Default")
      (node (ref "DS1") (pin "4") (pinfunction "C_4") (pintype "input"))
      (node (ref "R3") (pin "2") (pinfunction "2_2") (pintype "input"))
    )
    (net (code "26") (name "Net-(DS1-D)") (class "Default")
      (node (ref "DS1") (pin "2") (pinfunction "D_2") (pintype "input"))
      (node (ref "R4") (pin "2") (pinfunction "2_2") (pintype "input"))
    )
    (net (code "27") (name "Net-(DS1-DIG1)") (class "Default")
      (node (ref "DS1") (pin "12") (pinfunction "DIG1_12") (pintype "input"))
      (node (ref "Q1") (pin "3") (pinfunction "C_3") (pintype "input"))
    )
    (net (code "28") (name "Net-(DS1-DIG2)") (class "Default")
      (node (ref "DS1") (pin "9") (pinfunction "DIG2_9") (pintype "input"))
      (node (ref "Q2") (pin "3") (pinfunction "C_3") (pintype "input"))
    )
    (net (code "29") (name "Net-(DS1-DIG3)") (class "Default")
      (node (ref "DS1") (pin "8") (pinfunction "DIG3_8") (pintype "input"))
      (node (ref "Q3") (pin "3") (pinfunction "C_3") (pintype "input"))
    )
    (net (code "30") (name "Net-(DS1-DIG4)") (class "Default")
      (node (ref "DS1") (pin "6") (pinfunction "DIG4_6") (pintype "input"))
      (node (ref "Q4") (pin "3") (pinfunction "C_3") (pintype "input"))
    )
    (net (code "31") (name "Net-(DS1-DP)") (class "Default")
      (node (ref "DS1") (pin "3") (pinfunction "DP_3") (pintype "input"))
      (node (ref "R8") (pin "2") (pinfunction "2_2") (pintype "input"))
    )
    (net (code "32") (name "Net-(DS1-E)") (class "Default")
      (node (ref "DS1") (pin "1") (pinfunction "E_1") (pintype "input"))
      (node (ref "R5") (pin "2") (pinfunction "2_2") (pintype "input"))
    )
    (net (code "33") (name "Net-(DS1-F)") (class "Default")
      (node (ref "DS1") (pin "10") (pinfunction "F_10") (pintype "input"))
      (node (ref "R6") (pin "2") (pinfunction "2_2") (pintype "input"))
    )
    (net (code "34") (name "Net-(DS1-G)") (class "Default")
      (node (ref "DS1") (pin "5") (pinfunction "G_5") (pintype "input"))
      (node (ref "R7") (pin "2") (pinfunction "2_2") (pintype "input"))
    )
    (net (code "35") (name "Net-(H2-Pad1)") (class "Default")
      (node (ref "H2") (pin "1") (pinfunction "1_1") (pintype "unspecified"))
      (node (ref "R32") (pin "2") (pinfunction "2_2") (pintype "input"))
    )
    (net (code "36") (name "Net-(H2-Pad4)") (class "Default")
      (node (ref "H2") (pin "4") (pinfunction "4_4") (pintype "unspecified"))
      (node (ref "R33") (pin "2") (pinfunction "2_2") (pintype "input"))
    )
    (net (code "37") (name "Net-(LED2-Pad3)") (class "Default")
      (node (ref "LED2") (pin "3") (pinfunction "3_3") (pintype "unspecified"))
      (node (ref "R23") (pin "1") (pinfunction "1_1") (pintype "input"))
    )
    (net (code "38") (name "Net-(LED4-A)") (class "Default")
      (node (ref "LED4") (pin "2") (pinfunction "A_2") (pintype "input"))
      (node (ref "R19") (pin "2") (pinfunction "2_2") (pintype "input"))
    )
    (net (code "39") (name "Net-(LED4-C)") (class "Default")
      (node (ref "LED4") (pin "1") (pinfunction "C_1") (pintype "input"))
      (node (ref "LED5") (pin "2") (pinfunction "A_2") (pintype "input"))
      (node (ref "U13") (pin "1") (pinfunction "STAT_1") (pintype "input"))
    )
    (net (code "40") (name "Net-(LED5-C)") (class "Default")
      (node (ref "LED5") (pin "1") (pinfunction "C_1") (pintype "input"))
      (node (ref "R20") (pin "2") (pinfunction "2_2") (pintype "input"))
    )
    (net (code "41") (name "Net-(Q1-B)") (class "Default")
      (node (ref "Q1") (pin "1") (pinfunction "B_1") (pintype "input"))
      (node (ref "R24") (pin "2") (pinfunction "2_2") (pintype "input"))
    )
    (net (code "42") (name "Net-(Q2-B)") (class "Default")
      (node (ref "Q2") (pin "1") (pinfunction "B_1") (pintype "input"))
      (node (ref "R25") (pin "2") (pinfunction "2_2") (pintype "input"))
    )
    (net (code "43") (name "Net-(Q3-B)") (class "Default")
      (node (ref "Q3") (pin "1") (pinfunction "B_1") (pintype "input"))
      (node (ref "R26") (pin "2") (pinfunction "2_2") (pintype "input"))
    )
    (net (code "44") (name "Net-(Q4-B)") (class "Default")
      (node (ref "Q4") (pin "1") (pinfunction "B_1") (pintype "input"))
      (node (ref "R27") (pin "2") (pinfunction "2_2") (pintype "input"))
    )
    (net (code "45") (name "Net-(SPK1-+)") (class "Default")
      (node (ref "SPK1") (pin "1") (pinfunction "+_1") (pintype "input"))
      (node (ref "U11") (pin "18") (pinfunction "PWM-_18") (pintype "input"))
    )
    (net (code "46") (name "Net-(SPK1--)") (class "Default")
      (node (ref "SPK1") (pin "2") (pinfunction "-_2") (pintype "input"))
      (node (ref "U11") (pin "16") (pinfunction "PWM+/DAC#_16") (pintype "input"))
    )
    (net (code "47") (name "Net-(U3-RSTb)") (class "Default")
      (node (ref "R21") (pin "1") (pinfunction "1_1") (pintype "input"))
      (node (ref "U3") (pin "9") (pinfunction "RSTb_9") (pintype "unspecified"))
    )
    (net (code "48") (name "Net-(U6-VDD)") (class "Default")
      (node (ref "C25") (pin "2") (pinfunction "2_2") (pintype "input"))
      (node (ref "C27") (pin "2") (pinfunction "2_2") (pintype "input"))
      (node (ref "R28") (pin "2") (pinfunction "2_2") (pintype "input"))
      (node (ref "U6") (pin "1") (pinfunction "VDD_1") (pintype "unspecified"))
    )
    (net (code "49") (name "Net-(U10-BOOT0)") (class "Default")
      (node (ref "R22") (pin "1") (pinfunction "1_1") (pintype "input"))
      (node (ref "U10") (pin "44") (pinfunction "BOOT0_44") (pintype "unspecified"))
    )
    (net (code "50") (name "Net-(U10-NRST)") (class "Default")
      (node (ref "C22") (pin "2") (pinfunction "2_2") (pintype "input"))
      (node (ref "U10") (pin "7") (pinfunction "NRST_7") (pintype "unspecified"))
    )
    (net (code "51") (name "Net-(U10-PA13)") (class "Default")
      (node (ref "R33") (pin "1") (pinfunction "1_1") (pintype "input"))
      (node (ref "U10") (pin "34") (pinfunction "PA13_34") (pintype "unspecified"))
    )
    (net (code "52") (name "Net-(U10-PA14)") (class "Default")
      (node (ref "R32") (pin "1") (pinfunction "1_1") (pintype "input"))
      (node (ref "U10") (pin "37") (pinfunction "PA14_37") (pintype "unspecified"))
    )
    (net (code "53") (name "Net-(U10-PC14-OSC32IN)") (class "Default")
      (node (ref "C20") (pin "2") (pinfunction "2_2") (pintype "input"))
      (node (ref "U10") (pin "3") (pinfunction "PC14-OSC32IN_3") (pintype "unspecified"))
      (node (ref "X1") (pin "1") (pinfunction "1_1") (pintype "unspecified"))
    )
    (net (code "54") (name "Net-(U10-PC15-OSC32OUT)") (class "Default")
      (node (ref "C21") (pin "2") (pinfunction "2_2") (pintype "input"))
      (node (ref "U10") (pin "4") (pinfunction "PC15-OSC32OUT_4") (pintype "unspecified"))
      (node (ref "X1") (pin "2") (pinfunction "2_2") (pintype "unspecified"))
    )
    (net (code "55") (name "Net-(U10-VBAT)") (class "Default")
      (node (ref "H3") (pin "2") (pinfunction "2_2") (pintype "input"))
      (node (ref "U10") (pin "1") (pinfunction "VBAT_1") (pintype "unspecified"))
    )
    (net (code "56") (name "Net-(U10-VDDA)") (class "Default")
      (node (ref "R13") (pin "2") (pinfunction "2_2") (pintype "input"))
      (node (ref "U10") (pin "9") (pinfunction "VDDA_9") (pintype "unspecified"))
    )
    (net (code "57") (name "Net-(U11-CVDD)") (class "Default")
      (node (ref "C1") (pin "1") (pinfunction "1_1") (pintype "input"))
      (node (ref "U11") (pin "12") (pinfunction "CVDD_12") (pintype "input"))
    )
    (net (code "58") (name "Net-(U11-OSCI)") (class "Default")
      (node (ref "R11") (pin "1") (pinfunction "1_1") (pintype "input"))
      (node (ref "U11") (pin "13") (pinfunction "OSCI_13") (pintype "input"))
    )
    (net (code "59") (name "Net-(U12-IO2)") (class "Default")
      (node (ref "C7") (pin "2") (pinfunction "2_2") (pintype "input"))
      (node (ref "U12") (pin "3") (pinfunction "IO2_3") (pintype "unspecified"))
    )
    (net (code "60") (name "Net-(U13-PROG)") (class "Default")
      (node (ref "R18") (pin "1") (pinfunction "1_1") (pintype "input"))
      (node (ref "U13") (pin "5") (pinfunction "PROG_5") (pintype "input"))
    )
    (net (code "61") (name "Net-(USB1-CC1)") (class "Default")
      (node (ref "R9") (pin "2") (pinfunction "2_2") (pintype "input"))
      (node (ref "USB1") (pin "A5") (pinfunction "CC1_A5") (pintype "input"))
    )
    (net (code "62") (name "Net-(USB1-CC2)") (class "Default")
      (node (ref "R10") (pin "2") (pinfunction "2_2") (pintype "input"))
      (node (ref "USB1") (pin "B5") (pinfunction "CC2_B5") (pintype "input"))
    )
    (net (code "63") (name "PWR_EN") (class "Default")
      (node (ref "Q5") (pin "1") (pinfunction "G_1") (pintype "input"))
      (node (ref "R31") (pin "2") (pinfunction "2_2") (pintype "input"))
      (node (ref "U10") (pin "38") (pinfunction "PA15_38") (pintype "unspecified"))
    )
    (net (code "64") (name "RES_PHOTO") (class "Default")
      (node (ref "R34") (pin "2") (pinfunction "2_2") (pintype "input"))
      (node (ref "R35") (pin "1") (pinfunction "1_1") (pintype "input"))
      (node (ref "U10") (pin "14") (pinfunction "PA4_14") (pintype "unspecified"))
    )
    (net (code "65") (name "RXD") (class "Default")
      (node (ref "U10") (pin "21") (pinfunction "PB10_21") (pintype "unspecified"))
      (node (ref "U3") (pin "20") (pinfunction "RXD_20") (pintype "unspecified"))
    )
    (net (code "66") (name "SEGA") (class "Default")
      (node (ref "R1") (pin "1") (pinfunction "1_1") (pintype "input"))
      (node (ref "U10") (pin "18") (pinfunction "PB0_18") (pintype "unspecified"))
    )
    (net (code "67") (name "SEGB") (class "Default")
      (node (ref "R2") (pin "1") (pinfunction "1_1") (pintype "input"))
      (node (ref "U10") (pin "19") (pinfunction "PB1_19") (pintype "unspecified"))
    )
    (net (code "68") (name "SEGC") (class "Default")
      (node (ref "R3") (pin "1") (pinfunction "1_1") (pintype "input"))
      (node (ref "U10") (pin "20") (pinfunction "PB2_20") (pintype "unspecified"))
    )
    (net (code "69") (name "SEGD") (class "Default")
      (node (ref "R4") (pin "1") (pinfunction "1_1") (pintype "input"))
      (node (ref "U10") (pin "39") (pinfunction "PB3_39") (pintype "unspecified"))
    )
    (net (code "70") (name "SEGDP") (class "Default")
      (node (ref "R8") (pin "1") (pinfunction "1_1") (pintype "input"))
      (node (ref "U10") (pin "43") (pinfunction "PB7_43") (pintype "unspecified"))
    )
    (net (code "71") (name "SEGE") (class "Default")
      (node (ref "R5") (pin "1") (pinfunction "1_1") (pintype "input"))
      (node (ref "U10") (pin "40") (pinfunction "PB4_40") (pintype "unspecified"))
    )
    (net (code "72") (name "SEGF") (class "Default")
      (node (ref "R6") (pin "1") (pinfunction "1_1") (pintype "input"))
      (node (ref "U10") (pin "41") (pinfunction "PB5_41") (pintype "unspecified"))
    )
    (net (code "73") (name "SEGG") (class "Default")
      (node (ref "R7") (pin "1") (pinfunction "1_1") (pintype "input"))
      (node (ref "U10") (pin "42") (pinfunction "PB6_42") (pintype "unspecified"))
    )
    (net (code "74") (name "SPI_CS_AM") (class "Default")
      (node (ref "H1") (pin "1") (pinfunction "1_1") (pintype "unspecified"))
      (node (ref "U11") (pin "3") (pinfunction "P15_3") (pintype "input"))
      (node (ref "U12") (pin "1") (pinfunction "CS#_1") (pintype "unspecified"))
    )
    (net (code "75") (name "SPI_MISO") (class "Default")
      (node (ref "H1") (pin "2") (pinfunction "2_2") (pintype "unspecified"))
      (node (ref "U11") (pin "1") (pinfunction "P13_1") (pintype "input"))
      (node (ref "U12") (pin "2") (pinfunction "DO（IO1）_2") (pintype "unspecified"))
    )
    (net (code "76") (name "SPI_MOSI") (class "Default")
      (node (ref "H1") (pin "4") (pinfunction "4_4") (pintype "unspecified"))
      (node (ref "U11") (pin "2") (pinfunction "P14_2") (pintype "input"))
      (node (ref "U12") (pin "5") (pinfunction "DI（IO0）_5") (pintype "unspecified"))
    )
    (net (code "77") (name "SPI_SCK") (class "Default")
      (node (ref "H1") (pin "3") (pinfunction "3_3") (pintype "unspecified"))
      (node (ref "U11") (pin "4") (pinfunction "P16_4") (pintype "input"))
      (node (ref "U12") (pin "6") (pinfunction "CLK_6") (pintype "unspecified"))
    )
    (net (code "78") (name "TXD") (class "Default")
      (node (ref "U10") (pin "22") (pinfunction "PB11_22") (pintype "unspecified"))
      (node (ref "U3") (pin "21") (pinfunction "TXD_21") (pintype "unspecified"))
    )
    (net (code "79") (name "USB_DN") (class "Default")
      (node (ref "U3") (pin "4") (pinfunction "D-_4") (pintype "unspecified"))
      (node (ref "USB1") (pin "A7") (pinfunction "DN1_A7") (pintype "input"))
      (node (ref "USB1") (pin "B7") (pinfunction "DN2_B7") (pintype "input"))
    )
    (net (code "80") (name "USB_DP") (class "Default")
      (node (ref "U3") (pin "3") (pinfunction "D+_3") (pintype "unspecified"))
      (node (ref "USB1") (pin "A6") (pinfunction "DP1_A6") (pintype "input"))
      (node (ref "USB1") (pin "B6") (pinfunction "DP2_B6") (pintype "input"))
    )
    (net (code "81") (name "VBAT") (class "Default")
      (node (ref "C13") (pin "1") (pinfunction "1_1") (pintype "input"))
      (node (ref "C15") (pin "2") (pinfunction "2_2") (pintype "input"))
      (node (ref "C16") (pin "2") (pinfunction "2_2") (pintype "input"))
      (node (ref "CN1") (pin "1") (pinfunction "1_1") (pintype "unspecified"))
      (node (ref "U13") (pin "3") (pinfunction "VBAT_3") (pintype "input"))
      (node (ref "U15") (pin "1") (pinfunction "IN_1") (pintype "unspecified"))
      (node (ref "U15") (pin "3") (pinfunction "EN_3") (pintype "unspecified"))
    )
    (net (code "82") (name "VBUS") (class "Default")
      (node (ref "C14") (pin "1") (pinfunction "1_1") (pintype "input"))
      (node (ref "R19") (pin "1") (pinfunction "1_1") (pintype "input"))
      (node (ref "U13") (pin "4") (pinfunction "VDD_4") (pintype "input"))
      (node (ref "U3") (pin "7") (pinfunction "VREGIN_7") (pintype "unspecified"))
      (node (ref "U3") (pin "8") (pinfunction "VBUS_8") (pintype "unspecified"))
      (node (ref "USB1") (pin "A4") (pinfunction "VBUS_A4") (pintype "input"))
      (node (ref "USB1") (pin "A9") (pinfunction "VBUS_A9") (pintype "input"))
      (node (ref "USB1") (pin "B4") (pinfunction "VBUS_B4") (pintype "input"))
      (node (ref "USB1") (pin "B9") (pinfunction "VBUS_B9") (pintype "input"))
    )
    (net (code "83") (name "unconnected-(U3-CTS-Pad18)") (class "Default")
      (node (ref "U3") (pin "18") (pinfunction "CTS_18") (pintype "unspecified+no_connect"))
    )
    (net (code "84") (name "unconnected-(U3-DCD-Pad24)") (class "Default")
      (node (ref "U3") (pin "24") (pinfunction "DCD_24") (pintype "unspecified+no_connect"))
    )
    (net (code "85") (name "unconnected-(U3-DSR-Pad22)") (class "Default")
      (node (ref "U3") (pin "22") (pinfunction "DSR_22") (pintype "unspecified+no_connect"))
    )
    (net (code "86") (name "unconnected-(U3-DTR-Pad23)") (class "Default")
      (node (ref "U3") (pin "23") (pinfunction "DTR_23") (pintype "unspecified+no_connect"))
    )
    (net (code "87") (name "unconnected-(U3-GPIO.0{slash}TXT-Pad14)") (class "Default")
      (node (ref "U3") (pin "14") (pinfunction "GPIO.0/TXT_14") (pintype "unspecified+no_connect"))
    )
    (net (code "88") (name "unconnected-(U3-GPIO.1{slash}RXT-Pad13)") (class "Default")
      (node (ref "U3") (pin "13") (pinfunction "GPIO.1/RXT_13") (pintype "unspecified+no_connect"))
    )
    (net (code "89") (name "unconnected-(U3-GPIO.2{slash}RS485-Pad12)") (class "Default")
      (node (ref "U3") (pin "12") (pinfunction "GPIO.2/RS485_12") (pintype "unspecified+no_connect"))
    )
    (net (code "90") (name "unconnected-(U3-GPIO.3{slash}WAKEUP-Pad11)") (class "Default")
      (node (ref "U3") (pin "11") (pinfunction "GPIO.3/WAKEUP_11") (pintype "unspecified+no_connect"))
    )
    (net (code "91") (name "unconnected-(U3-NC-Pad10)") (class "Default")
      (node (ref "U3") (pin "10") (pinfunction "NC_10") (pintype "unspecified+no_connect"))
    )
    (net (code "92") (name "unconnected-(U3-NC-Pad16)") (class "Default")
      (node (ref "U3") (pin "16") (pinfunction "NC_16") (pintype "unspecified+no_connect"))
    )
    (net (code "93") (name "unconnected-(U3-RI{slash}CLK-Pad1)") (class "Default")
      (node (ref "U3") (pin "1") (pinfunction "RI/CLK_1") (pintype "unspecified+no_connect"))
    )
    (net (code "94") (name "unconnected-(U3-RTS-Pad19)") (class "Default")
      (node (ref "U3") (pin "19") (pinfunction "RTS_19") (pintype "unspecified+no_connect"))
    )
    (net (code "95") (name "unconnected-(U3-SUSPEND-Pad17)") (class "Default")
      (node (ref "U3") (pin "17") (pinfunction "SUSPEND_17") (pintype "unspecified+no_connect"))
    )
    (net (code "96") (name "unconnected-(U3-SUSPENDb-Pad15)") (class "Default")
      (node (ref "U3") (pin "15") (pinfunction "SUSPENDb_15") (pintype "unspecified+no_connect"))
    )
    (net (code "97") (name "unconnected-(U5-NC-Pad3)") (class "Default")
      (node (ref "U5") (pin "3") (pinfunction "NC_3") (pintype "unspecified+no_connect"))
    )
    (net (code "98") (name "unconnected-(U5-NC-Pad4)") (class "Default")
      (node (ref "U5") (pin "4") (pinfunction "NC_4") (pintype "unspecified+no_connect"))
    )
    (net (code "99") (name "unconnected-(U6-n{slash}a-Pad4)") (class "Default")
      (node (ref "U6") (pin "4") (pinfunction "n/a_4") (pintype "unspecified+no_connect"))
    )
    (net (code "100") (name "unconnected-(U10-PC13-TAMPER-RTC-Pad2)") (class "Default")
      (node (ref "U10") (pin "2") (pinfunction "PC13-TAMPER-RTC_2") (pintype "unspecified+no_connect"))
    )
    (net (code "101") (name "unconnected-(U10-PD0-OSCIN-Pad5)") (class "Default")
      (node (ref "U10") (pin "5") (pinfunction "PD0-OSCIN_5") (pintype "unspecified+no_connect"))
    )
    (net (code "102") (name "unconnected-(U10-PD1-OSCOUT-Pad6)") (class "Default")
      (node (ref "U10") (pin "6") (pinfunction "PD1-OSCOUT_6") (pintype "unspecified+no_connect"))
    )
    (net (code "103") (name "unconnected-(U11-NC-Pad20)") (class "Default")
      (node (ref "U11") (pin "20") (pinfunction "NC_20") (pintype "input+no_connect"))
    )
    (net (code "104") (name "unconnected-(U11-P00-Pad6)") (class "Default")
      (node (ref "U11") (pin "6") (pinfunction "P00_6") (pintype "input+no_connect"))
    )
    (net (code "105") (name "unconnected-(U15-NC-Pad4)") (class "Default")
      (node (ref "U15") (pin "4") (pinfunction "NC_4") (pintype "unspecified+no_connect"))
    )
    (net (code "106") (name "unconnected-(USB1-SBUS1-PadA8)") (class "Default")
      (node (ref "USB1") (pin "A8") (pinfunction "SBUS1_A8") (pintype "input+no_connect"))
    )
    (net (code "107") (name "unconnected-(USB1-SBUS2-PadB8)") (class "Default")
      (node (ref "USB1") (pin "B8") (pinfunction "SBUS2_B8") (pintype "input+no_connect"))
    )
  )
)
